# 21-de-77.net
KiCad netlist of a schematic drawn in EAGLE
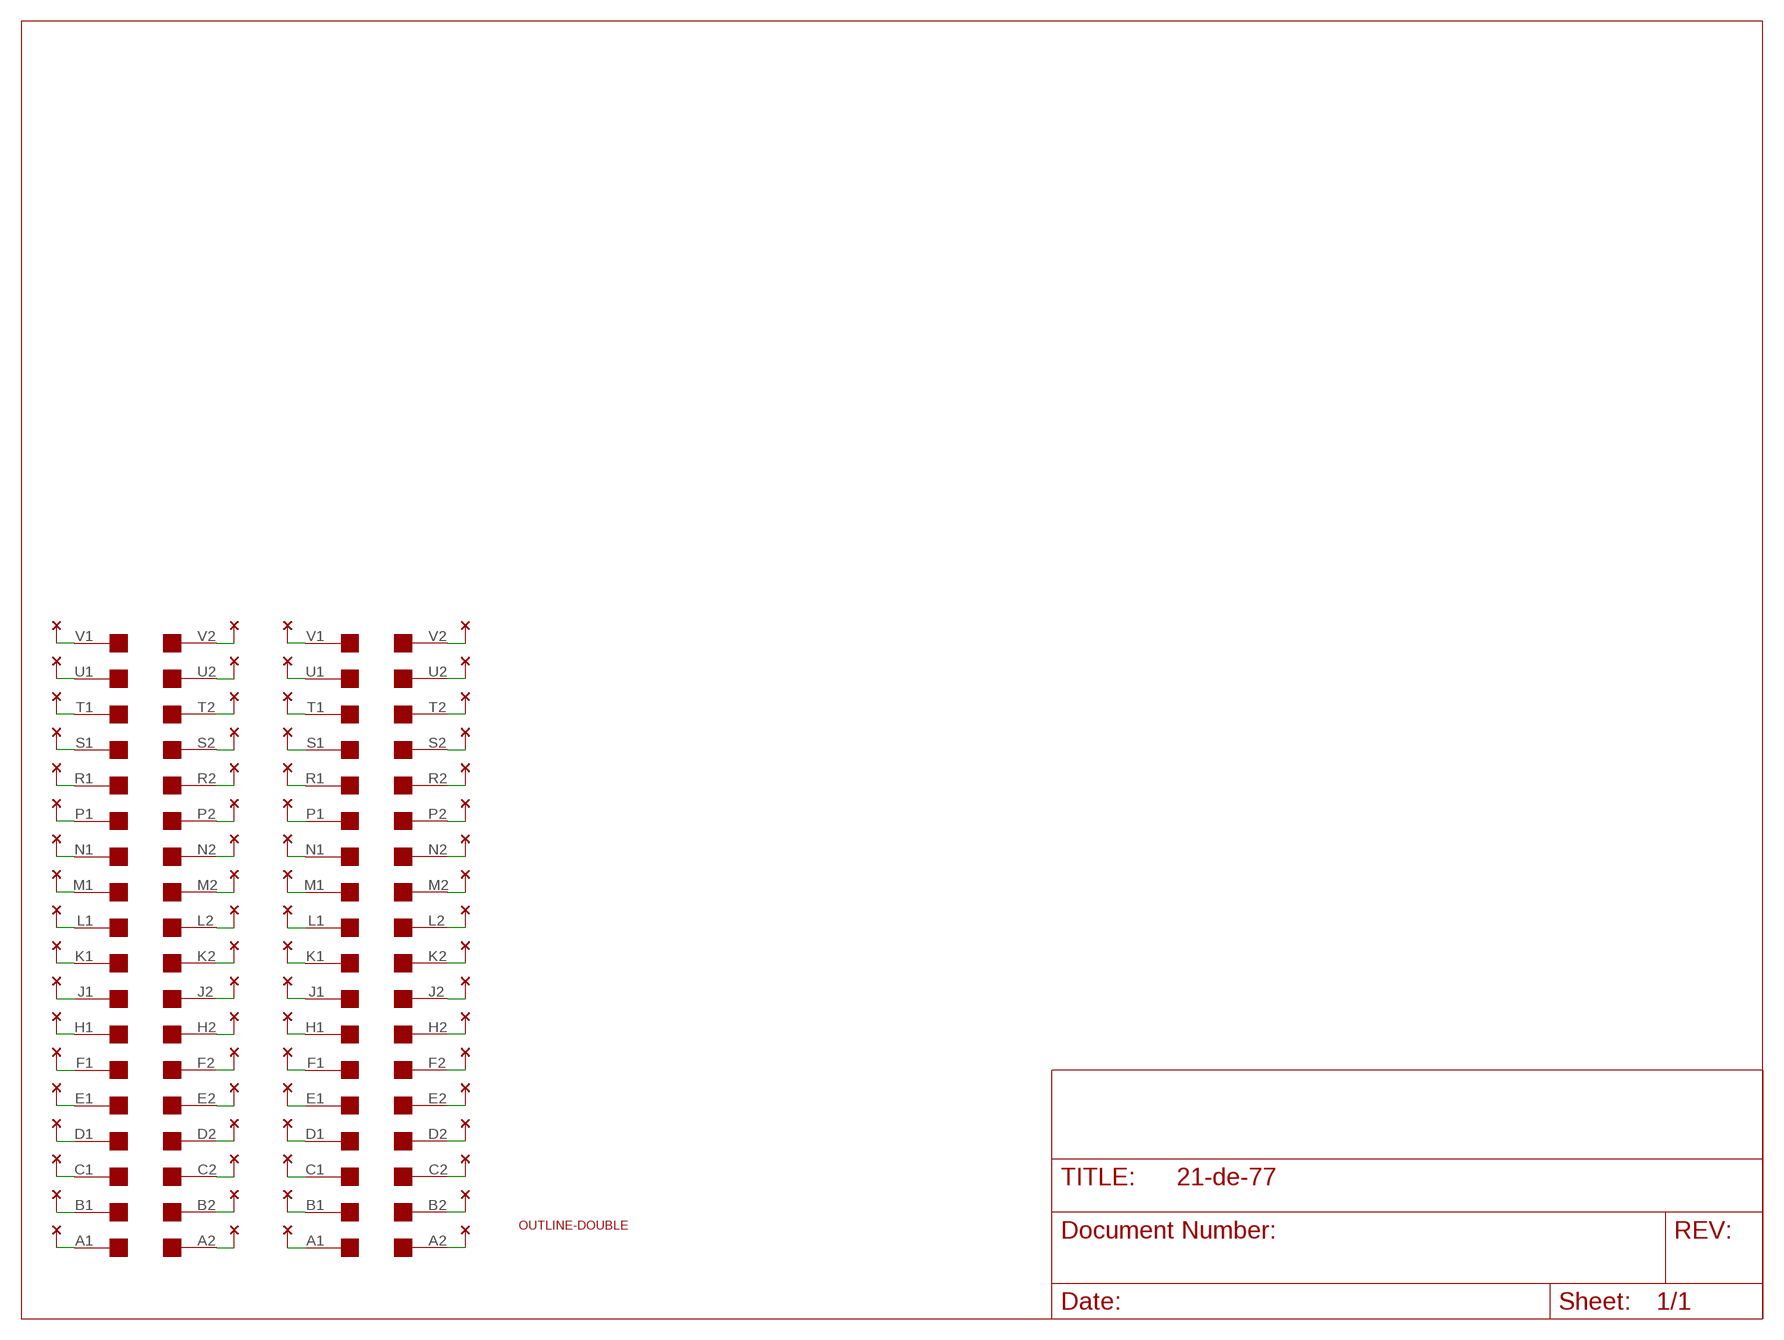
[diagram p0: schematic, sheet 1]

(export (version "E")
  (design (tool "Eeschema 10.0.6"))
  (components
    (comp (ref "U$1")
      (value "SINGLE")
      (footprint "eagle-import:EDGE-CON2")
      (libsource (lib "eagle-import") (part "SINGLE"))
    )
    (comp (ref "U$3")
      (value "THRU-HOLE2C")
      (footprint "eagle-import:THRU-HOLEC")
      (libsource (lib "eagle-import") (part "THRU-HOLE2C"))
    )
    (comp (ref "U$4")
      (value "OUTLINE-DOUBLE")
      (footprint "eagle-import:DOUBLE")
      (libsource (lib "eagle-import") (part "OUTLINE-DOUBLE"))
    )
    (comp (ref "U$5")
      (value "THRU-HOLE2C")
      (footprint "eagle-import:THRU-HOLEC")
      (libsource (lib "eagle-import") (part "THRU-HOLE2C"))
    )
    (comp (ref "U$6")
      (value "SINGLE")
      (footprint "eagle-import:EDGE-CON2")
      (libsource (lib "eagle-import") (part "SINGLE"))
    )
  )
  (nets
    (net (code "1") (name "Net-(U$1A-1)") (class "Default")
      (node (ref "U$1") (pin "A1") (pinfunction "1_A1") (pintype "bidirectional"))
      (node (ref "U$3") (pin "A1") (pinfunction "P$1_A1") (pintype "passive"))
    )
    (net (code "2") (name "Net-(U$1AA-1)") (class "Default")
      (node (ref "U$1") (pin "R1") (pinfunction "1_R1") (pintype "bidirectional"))
      (node (ref "U$3") (pin "R1") (pinfunction "P$1_R1") (pintype "passive"))
    )
    (net (code "3") (name "Net-(U$1AB-1)") (class "Default")
      (node (ref "U$1") (pin "R2") (pinfunction "1_R2") (pintype "bidirectional"))
      (node (ref "U$3") (pin "R2") (pinfunction "P$1_R2") (pintype "passive"))
    )
    (net (code "4") (name "Net-(U$1AC-1)") (class "Default")
      (node (ref "U$1") (pin "S1") (pinfunction "1_S1") (pintype "bidirectional"))
      (node (ref "U$3") (pin "S1") (pinfunction "P$1_S1") (pintype "passive"))
    )
    (net (code "5") (name "Net-(U$1AD-1)") (class "Default")
      (node (ref "U$1") (pin "S2") (pinfunction "1_S2") (pintype "bidirectional"))
      (node (ref "U$3") (pin "S2") (pinfunction "P$1_S2") (pintype "passive"))
    )
    (net (code "6") (name "Net-(U$1AE-1)") (class "Default")
      (node (ref "U$1") (pin "T1") (pinfunction "1_T1") (pintype "bidirectional"))
      (node (ref "U$3") (pin "T1") (pinfunction "P$1_T1") (pintype "passive"))
    )
    (net (code "7") (name "Net-(U$1AF-1)") (class "Default")
      (node (ref "U$1") (pin "T2") (pinfunction "1_T2") (pintype "bidirectional"))
      (node (ref "U$3") (pin "T2") (pinfunction "P$1_T2") (pintype "passive"))
    )
    (net (code "8") (name "Net-(U$1AG-1)") (class "Default")
      (node (ref "U$1") (pin "U1") (pinfunction "1_U1") (pintype "bidirectional"))
      (node (ref "U$3") (pin "U1") (pinfunction "P$1_U1") (pintype "passive"))
    )
    (net (code "9") (name "Net-(U$1AH-1)") (class "Default")
      (node (ref "U$1") (pin "U2") (pinfunction "1_U2") (pintype "bidirectional"))
      (node (ref "U$3") (pin "U2") (pinfunction "P$1_U2") (pintype "passive"))
    )
    (net (code "10") (name "Net-(U$1AI-1)") (class "Default")
      (node (ref "U$1") (pin "V1") (pinfunction "1_V1") (pintype "bidirectional"))
      (node (ref "U$3") (pin "V1") (pinfunction "P$1_V1") (pintype "passive"))
    )
    (net (code "11") (name "Net-(U$1AJ-1)") (class "Default")
      (node (ref "U$1") (pin "V2") (pinfunction "1_V2") (pintype "bidirectional"))
      (node (ref "U$3") (pin "V2") (pinfunction "P$1_V2") (pintype "passive"))
    )
    (net (code "12") (name "Net-(U$1B-1)") (class "Default")
      (node (ref "U$1") (pin "A2") (pinfunction "1_A2") (pintype "bidirectional"))
      (node (ref "U$3") (pin "A2") (pinfunction "P$1_A2") (pintype "passive"))
    )
    (net (code "13") (name "Net-(U$1C-1)") (class "Default")
      (node (ref "U$1") (pin "B1") (pinfunction "1_B1") (pintype "bidirectional"))
      (node (ref "U$3") (pin "B1") (pinfunction "P$1_B1") (pintype "passive"))
    )
    (net (code "14") (name "Net-(U$1D-1)") (class "Default")
      (node (ref "U$1") (pin "B2") (pinfunction "1_B2") (pintype "bidirectional"))
      (node (ref "U$3") (pin "B2") (pinfunction "P$1_B2") (pintype "passive"))
    )
    (net (code "15") (name "Net-(U$1E-1)") (class "Default")
      (node (ref "U$1") (pin "C1") (pinfunction "1_C1") (pintype "bidirectional"))
      (node (ref "U$3") (pin "C1") (pinfunction "P$1_C1") (pintype "passive"))
    )
    (net (code "16") (name "Net-(U$1F-1)") (class "Default")
      (node (ref "U$1") (pin "C2") (pinfunction "1_C2") (pintype "bidirectional"))
      (node (ref "U$3") (pin "C2") (pinfunction "P$1_C2") (pintype "passive"))
    )
    (net (code "17") (name "Net-(U$1G-1)") (class "Default")
      (node (ref "U$1") (pin "D1") (pinfunction "1_D1") (pintype "bidirectional"))
      (node (ref "U$3") (pin "D1") (pinfunction "P$1_D1") (pintype "passive"))
    )
    (net (code "18") (name "Net-(U$1H-1)") (class "Default")
      (node (ref "U$1") (pin "D2") (pinfunction "1_D2") (pintype "bidirectional"))
      (node (ref "U$3") (pin "D2") (pinfunction "P$1_D2") (pintype "passive"))
    )
    (net (code "19") (name "Net-(U$1I-1)") (class "Default")
      (node (ref "U$1") (pin "E1") (pinfunction "1_E1") (pintype "bidirectional"))
      (node (ref "U$3") (pin "E1") (pinfunction "P$1_E1") (pintype "passive"))
    )
    (net (code "20") (name "Net-(U$1J-1)") (class "Default")
      (node (ref "U$1") (pin "E2") (pinfunction "1_E2") (pintype "bidirectional"))
      (node (ref "U$3") (pin "E2") (pinfunction "P$1_E2") (pintype "passive"))
    )
    (net (code "21") (name "Net-(U$1K-1)") (class "Default")
      (node (ref "U$1") (pin "F1") (pinfunction "1_F1") (pintype "bidirectional"))
      (node (ref "U$3") (pin "F1") (pinfunction "P$1_F1") (pintype "passive"))
    )
    (net (code "22") (name "Net-(U$1L-1)") (class "Default")
      (node (ref "U$1") (pin "F2") (pinfunction "1_F2") (pintype "bidirectional"))
      (node (ref "U$3") (pin "F2") (pinfunction "P$1_F2") (pintype "passive"))
    )
    (net (code "23") (name "Net-(U$1M-1)") (class "Default")
      (node (ref "U$1") (pin "H1") (pinfunction "1_H1") (pintype "bidirectional"))
      (node (ref "U$3") (pin "H1") (pinfunction "P$1_H1") (pintype "passive"))
    )
    (net (code "24") (name "Net-(U$1N-1)") (class "Default")
      (node (ref "U$1") (pin "H2") (pinfunction "1_H2") (pintype "bidirectional"))
      (node (ref "U$3") (pin "H2") (pinfunction "P$1_H2") (pintype "passive"))
    )
    (net (code "25") (name "Net-(U$1O-1)") (class "Default")
      (node (ref "U$1") (pin "J1") (pinfunction "1_J1") (pintype "bidirectional"))
      (node (ref "U$3") (pin "J1") (pinfunction "P$1_J1") (pintype "passive"))
    )
    (net (code "26") (name "Net-(U$1P-1)") (class "Default")
      (node (ref "U$1") (pin "J2") (pinfunction "1_J2") (pintype "bidirectional"))
      (node (ref "U$3") (pin "J2") (pinfunction "P$1_J2") (pintype "passive"))
    )
    (net (code "27") (name "Net-(U$1Q-1)") (class "Default")
      (node (ref "U$1") (pin "K1") (pinfunction "1_K1") (pintype "bidirectional"))
      (node (ref "U$3") (pin "K1") (pinfunction "P$1_K1") (pintype "passive"))
    )
    (net (code "28") (name "Net-(U$1R-1)") (class "Default")
      (node (ref "U$1") (pin "K2") (pinfunction "1_K2") (pintype "bidirectional"))
      (node (ref "U$3") (pin "K2") (pinfunction "P$1_K2") (pintype "passive"))
    )
    (net (code "29") (name "Net-(U$1S-1)") (class "Default")
      (node (ref "U$1") (pin "L1") (pinfunction "1_L1") (pintype "bidirectional"))
      (node (ref "U$3") (pin "L1") (pinfunction "P$1_L1") (pintype "passive"))
    )
    (net (code "30") (name "Net-(U$1T-1)") (class "Default")
      (node (ref "U$1") (pin "L2") (pinfunction "1_L2") (pintype "bidirectional"))
      (node (ref "U$3") (pin "L2") (pinfunction "P$1_L2") (pintype "passive"))
    )
    (net (code "31") (name "Net-(U$1U-1)") (class "Default")
      (node (ref "U$1") (pin "M1") (pinfunction "1_M1") (pintype "bidirectional"))
      (node (ref "U$3") (pin "M1") (pinfunction "P$1_M1") (pintype "passive"))
    )
    (net (code "32") (name "Net-(U$1V-1)") (class "Default")
      (node (ref "U$1") (pin "M2") (pinfunction "1_M2") (pintype "bidirectional"))
      (node (ref "U$3") (pin "M2") (pinfunction "P$1_M2") (pintype "passive"))
    )
    (net (code "33") (name "Net-(U$1W-1)") (class "Default")
      (node (ref "U$1") (pin "N1") (pinfunction "1_N1") (pintype "bidirectional"))
      (node (ref "U$3") (pin "N1") (pinfunction "P$1_N1") (pintype "passive"))
    )
    (net (code "34") (name "Net-(U$1X-1)") (class "Default")
      (node (ref "U$1") (pin "N2") (pinfunction "1_N2") (pintype "bidirectional"))
      (node (ref "U$3") (pin "N2") (pinfunction "P$1_N2") (pintype "passive"))
    )
    (net (code "35") (name "Net-(U$1Y-1)") (class "Default")
      (node (ref "U$1") (pin "P1") (pinfunction "1_P1") (pintype "bidirectional"))
      (node (ref "U$3") (pin "P1") (pinfunction "P$1_P1") (pintype "passive"))
    )
    (net (code "36") (name "Net-(U$1Z-1)") (class "Default")
      (node (ref "U$1") (pin "P2") (pinfunction "1_P2") (pintype "bidirectional"))
      (node (ref "U$3") (pin "P2") (pinfunction "P$1_P2") (pintype "passive"))
    )
    (net (code "37") (name "Net-(U$5A-P$1)") (class "Default")
      (node (ref "U$5") (pin "A1") (pinfunction "P$1_A1") (pintype "passive"))
      (node (ref "U$6") (pin "A1") (pinfunction "1_A1") (pintype "bidirectional"))
    )
    (net (code "38") (name "Net-(U$5AA-P$1)") (class "Default")
      (node (ref "U$5") (pin "R1") (pinfunction "P$1_R1") (pintype "passive"))
      (node (ref "U$6") (pin "R1") (pinfunction "1_R1") (pintype "bidirectional"))
    )
    (net (code "39") (name "Net-(U$5AB-P$1)") (class "Default")
      (node (ref "U$5") (pin "R2") (pinfunction "P$1_R2") (pintype "passive"))
      (node (ref "U$6") (pin "R2") (pinfunction "1_R2") (pintype "bidirectional"))
    )
    (net (code "40") (name "Net-(U$5AC-P$1)") (class "Default")
      (node (ref "U$5") (pin "S1") (pinfunction "P$1_S1") (pintype "passive"))
      (node (ref "U$6") (pin "S1") (pinfunction "1_S1") (pintype "bidirectional"))
    )
    (net (code "41") (name "Net-(U$5AD-P$1)") (class "Default")
      (node (ref "U$5") (pin "S2") (pinfunction "P$1_S2") (pintype "passive"))
      (node (ref "U$6") (pin "S2") (pinfunction "1_S2") (pintype "bidirectional"))
    )
    (net (code "42") (name "Net-(U$5AE-P$1)") (class "Default")
      (node (ref "U$5") (pin "T1") (pinfunction "P$1_T1") (pintype "passive"))
      (node (ref "U$6") (pin "T1") (pinfunction "1_T1") (pintype "bidirectional"))
    )
    (net (code "43") (name "Net-(U$5AF-P$1)") (class "Default")
      (node (ref "U$5") (pin "T2") (pinfunction "P$1_T2") (pintype "passive"))
      (node (ref "U$6") (pin "T2") (pinfunction "1_T2") (pintype "bidirectional"))
    )
    (net (code "44") (name "Net-(U$5AG-P$1)") (class "Default")
      (node (ref "U$5") (pin "U1") (pinfunction "P$1_U1") (pintype "passive"))
      (node (ref "U$6") (pin "U1") (pinfunction "1_U1") (pintype "bidirectional"))
    )
    (net (code "45") (name "Net-(U$5AH-P$1)") (class "Default")
      (node (ref "U$5") (pin "U2") (pinfunction "P$1_U2") (pintype "passive"))
      (node (ref "U$6") (pin "U2") (pinfunction "1_U2") (pintype "bidirectional"))
    )
    (net (code "46") (name "Net-(U$5AI-P$1)") (class "Default")
      (node (ref "U$5") (pin "V1") (pinfunction "P$1_V1") (pintype "passive"))
      (node (ref "U$6") (pin "V1") (pinfunction "1_V1") (pintype "bidirectional"))
    )
    (net (code "47") (name "Net-(U$5AJ-P$1)") (class "Default")
      (node (ref "U$5") (pin "V2") (pinfunction "P$1_V2") (pintype "passive"))
      (node (ref "U$6") (pin "V2") (pinfunction "1_V2") (pintype "bidirectional"))
    )
    (net (code "48") (name "Net-(U$5B-P$1)") (class "Default")
      (node (ref "U$5") (pin "A2") (pinfunction "P$1_A2") (pintype "passive"))
      (node (ref "U$6") (pin "A2") (pinfunction "1_A2") (pintype "bidirectional"))
    )
    (net (code "49") (name "Net-(U$5C-P$1)") (class "Default")
      (node (ref "U$5") (pin "B1") (pinfunction "P$1_B1") (pintype "passive"))
      (node (ref "U$6") (pin "B1") (pinfunction "1_B1") (pintype "bidirectional"))
    )
    (net (code "50") (name "Net-(U$5D-P$1)") (class "Default")
      (node (ref "U$5") (pin "B2") (pinfunction "P$1_B2") (pintype "passive"))
      (node (ref "U$6") (pin "B2") (pinfunction "1_B2") (pintype "bidirectional"))
    )
    (net (code "51") (name "Net-(U$5E-P$1)") (class "Default")
      (node (ref "U$5") (pin "C1") (pinfunction "P$1_C1") (pintype "passive"))
      (node (ref "U$6") (pin "C1") (pinfunction "1_C1") (pintype "bidirectional"))
    )
    (net (code "52") (name "Net-(U$5F-P$1)") (class "Default")
      (node (ref "U$5") (pin "C2") (pinfunction "P$1_C2") (pintype "passive"))
      (node (ref "U$6") (pin "C2") (pinfunction "1_C2") (pintype "bidirectional"))
    )
    (net (code "53") (name "Net-(U$5G-P$1)") (class "Default")
      (node (ref "U$5") (pin "D1") (pinfunction "P$1_D1") (pintype "passive"))
      (node (ref "U$6") (pin "D1") (pinfunction "1_D1") (pintype "bidirectional"))
    )
    (net (code "54") (name "Net-(U$5H-P$1)") (class "Default")
      (node (ref "U$5") (pin "D2") (pinfunction "P$1_D2") (pintype "passive"))
      (node (ref "U$6") (pin "D2") (pinfunction "1_D2") (pintype "bidirectional"))
    )
    (net (code "55") (name "Net-(U$5I-P$1)") (class "Default")
      (node (ref "U$5") (pin "E1") (pinfunction "P$1_E1") (pintype "passive"))
      (node (ref "U$6") (pin "E1") (pinfunction "1_E1") (pintype "bidirectional"))
    )
    (net (code "56") (name "Net-(U$5J-P$1)") (class "Default")
      (node (ref "U$5") (pin "E2") (pinfunction "P$1_E2") (pintype "passive"))
      (node (ref "U$6") (pin "E2") (pinfunction "1_E2") (pintype "bidirectional"))
    )
    (net (code "57") (name "Net-(U$5K-P$1)") (class "Default")
      (node (ref "U$5") (pin "F1") (pinfunction "P$1_F1") (pintype "passive"))
      (node (ref "U$6") (pin "F1") (pinfunction "1_F1") (pintype "bidirectional"))
    )
    (net (code "58") (name "Net-(U$5L-P$1)") (class "Default")
      (node (ref "U$5") (pin "F2") (pinfunction "P$1_F2") (pintype "passive"))
      (node (ref "U$6") (pin "F2") (pinfunction "1_F2") (pintype "bidirectional"))
    )
    (net (code "59") (name "Net-(U$5M-P$1)") (class "Default")
      (node (ref "U$5") (pin "H1") (pinfunction "P$1_H1") (pintype "passive"))
      (node (ref "U$6") (pin "H1") (pinfunction "1_H1") (pintype "bidirectional"))
    )
    (net (code "60") (name "Net-(U$5N-P$1)") (class "Default")
      (node (ref "U$5") (pin "H2") (pinfunction "P$1_H2") (pintype "passive"))
      (node (ref "U$6") (pin "H2") (pinfunction "1_H2") (pintype "bidirectional"))
    )
    (net (code "61") (name "Net-(U$5O-P$1)") (class "Default")
      (node (ref "U$5") (pin "J1") (pinfunction "P$1_J1") (pintype "passive"))
      (node (ref "U$6") (pin "J1") (pinfunction "1_J1") (pintype "bidirectional"))
    )
    (net (code "62") (name "Net-(U$5P-P$1)") (class "Default")
      (node (ref "U$5") (pin "J2") (pinfunction "P$1_J2") (pintype "passive"))
      (node (ref "U$6") (pin "J2") (pinfunction "1_J2") (pintype "bidirectional"))
    )
    (net (code "63") (name "Net-(U$5Q-P$1)") (class "Default")
      (node (ref "U$5") (pin "K1") (pinfunction "P$1_K1") (pintype "passive"))
      (node (ref "U$6") (pin "K1") (pinfunction "1_K1") (pintype "bidirectional"))
    )
    (net (code "64") (name "Net-(U$5R-P$1)") (class "Default")
      (node (ref "U$5") (pin "K2") (pinfunction "P$1_K2") (pintype "passive"))
      (node (ref "U$6") (pin "K2") (pinfunction "1_K2") (pintype "bidirectional"))
    )
    (net (code "65") (name "Net-(U$5S-P$1)") (class "Default")
      (node (ref "U$5") (pin "L1") (pinfunction "P$1_L1") (pintype "passive"))
      (node (ref "U$6") (pin "L1") (pinfunction "1_L1") (pintype "bidirectional"))
    )
    (net (code "66") (name "Net-(U$5T-P$1)") (class "Default")
      (node (ref "U$5") (pin "L2") (pinfunction "P$1_L2") (pintype "passive"))
      (node (ref "U$6") (pin "L2") (pinfunction "1_L2") (pintype "bidirectional"))
    )
    (net (code "67") (name "Net-(U$5U-P$1)") (class "Default")
      (node (ref "U$5") (pin "M1") (pinfunction "P$1_M1") (pintype "passive"))
      (node (ref "U$6") (pin "M1") (pinfunction "1_M1") (pintype "bidirectional"))
    )
    (net (code "68") (name "Net-(U$5V-P$1)") (class "Default")
      (node (ref "U$5") (pin "M2") (pinfunction "P$1_M2") (pintype "passive"))
      (node (ref "U$6") (pin "M2") (pinfunction "1_M2") (pintype "bidirectional"))
    )
    (net (code "69") (name "Net-(U$5W-P$1)") (class "Default")
      (node (ref "U$5") (pin "N1") (pinfunction "P$1_N1") (pintype "passive"))
      (node (ref "U$6") (pin "N1") (pinfunction "1_N1") (pintype "bidirectional"))
    )
    (net (code "70") (name "Net-(U$5X-P$1)") (class "Default")
      (node (ref "U$5") (pin "N2") (pinfunction "P$1_N2") (pintype "passive"))
      (node (ref "U$6") (pin "N2") (pinfunction "1_N2") (pintype "bidirectional"))
    )
    (net (code "71") (name "Net-(U$5Y-P$1)") (class "Default")
      (node (ref "U$5") (pin "P1") (pinfunction "P$1_P1") (pintype "passive"))
      (node (ref "U$6") (pin "P1") (pinfunction "1_P1") (pintype "bidirectional"))
    )
    (net (code "72") (name "Net-(U$5Z-P$1)") (class "Default")
      (node (ref "U$5") (pin "P2") (pinfunction "P$1_P2") (pintype "passive"))
      (node (ref "U$6") (pin "P2") (pinfunction "1_P2") (pintype "bidirectional"))
    )
  )
)
